# Adafruit_BQ24074.net
KiCad netlist of a schematic drawn in EAGLE
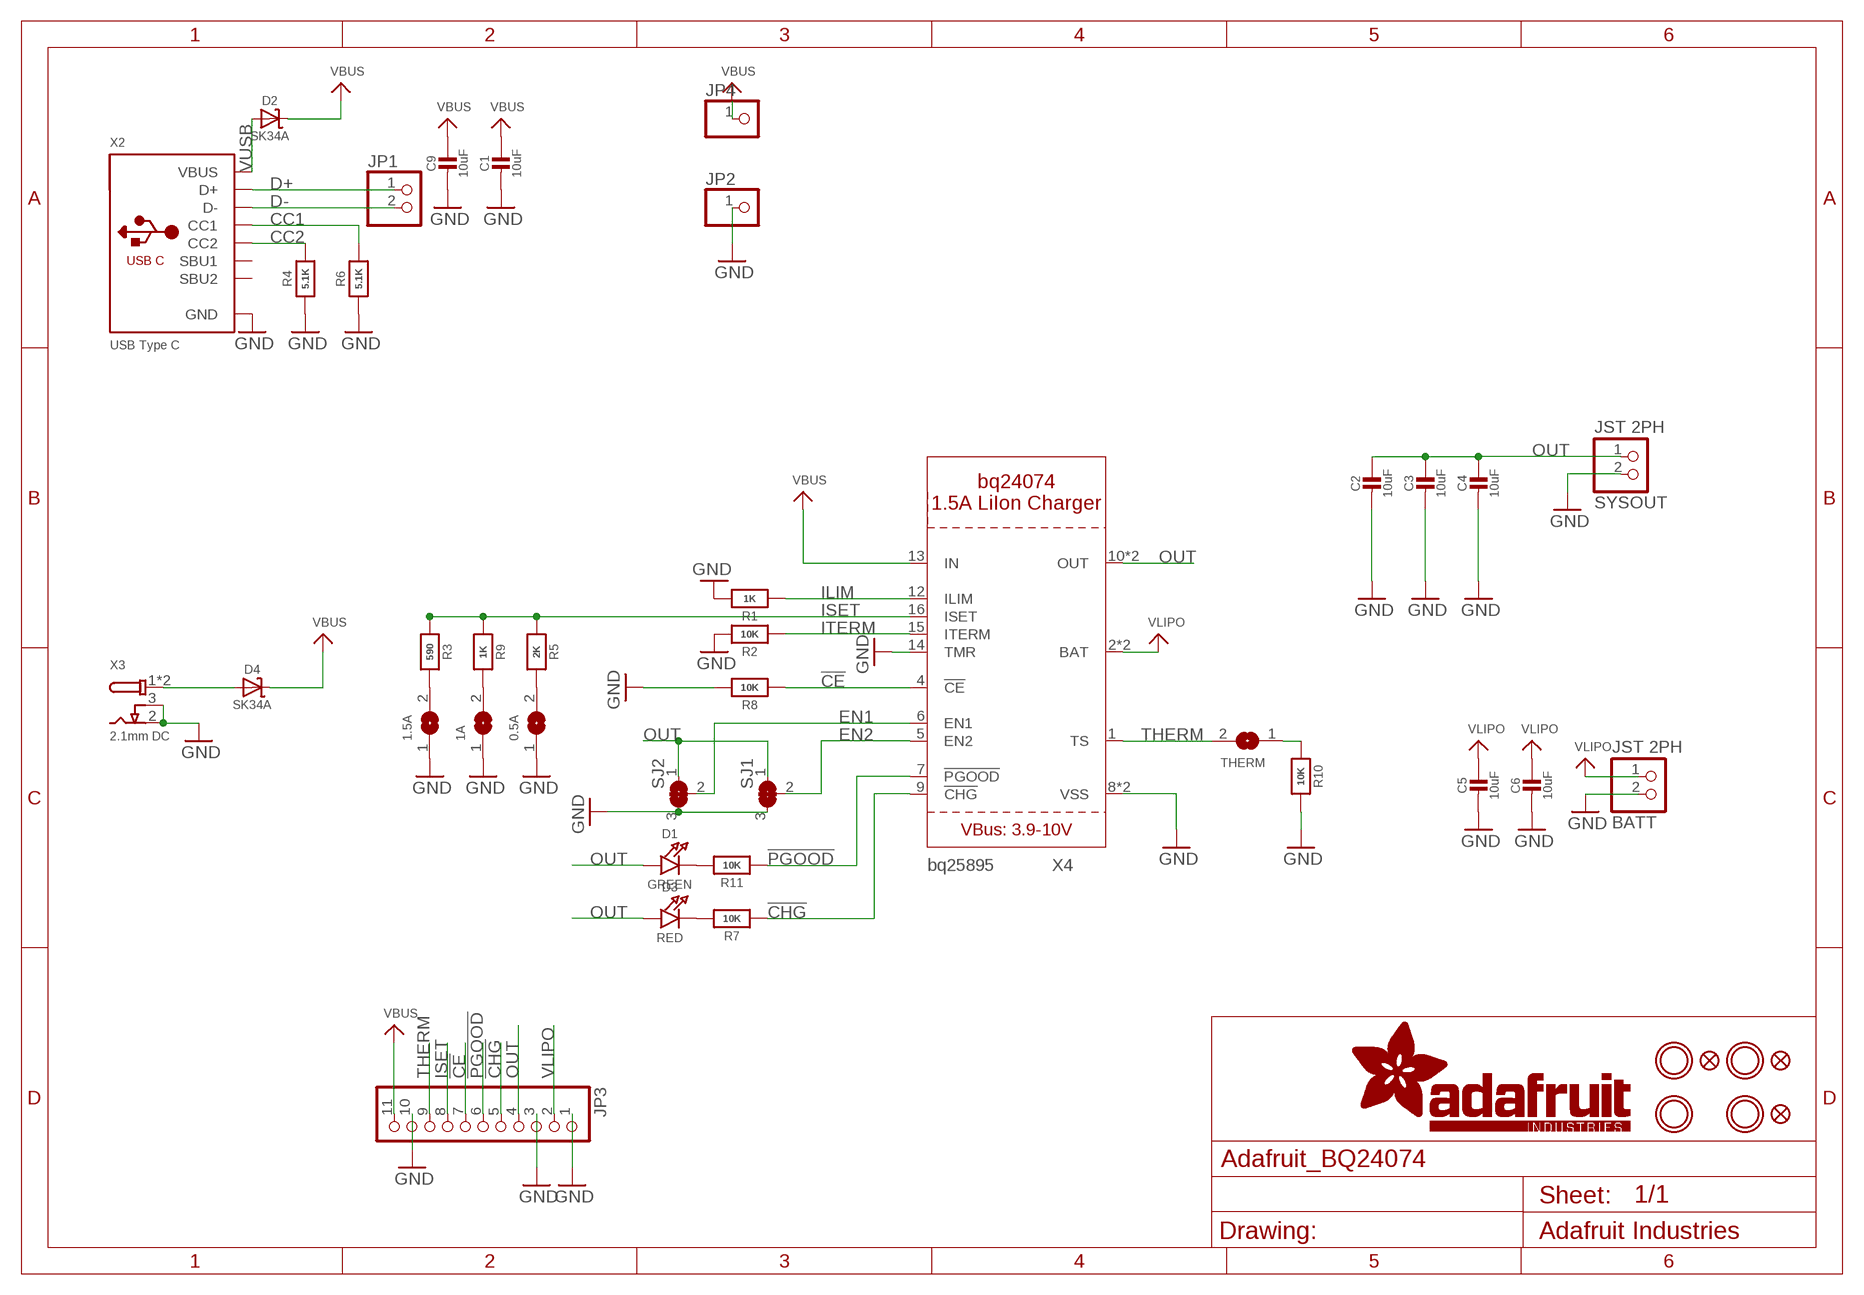
[diagram p0: schematic, sheet 1]

(export (version "E")
  (design (tool "Eeschema 10.0.6"))
  (components
    (comp (ref "0.5A")
      (value "SOLDERJUMPER")
      (footprint "eagle-import:SOLDERJUMPER_ARROW_NOPASTE")
      (libsource (lib "eagle-import") (part "SOLDERJUMPER"))
    )
    (comp (ref "1.5A")
      (value "SOLDERJUMPER")
      (footprint "eagle-import:SOLDERJUMPER_ARROW_NOPASTE")
      (libsource (lib "eagle-import") (part "SOLDERJUMPER"))
    )
    (comp (ref "1A")
      (value "SOLDERJUMPERCLOSED")
      (footprint "eagle-import:SOLDERJUMPER_CLOSEDWIRE")
      (libsource (lib "eagle-import") (part "SOLDERJUMPERCLOSED"))
    )
    (comp (ref "BATT")
      (value "JST 2PH")
      (footprint "eagle-import:JST-PH-2-SMT-RA")
      (libsource (lib "eagle-import") (part "JST_2PIN-SMT-RA"))
    )
    (comp (ref "C1")
      (value "10uF")
      (footprint "eagle-import:0805-NO")
      (libsource (lib "eagle-import") (part "CAP_CERAMIC0805-NOOUTLINE"))
    )
    (comp (ref "C2")
      (value "10uF")
      (footprint "eagle-import:0805-NO")
      (libsource (lib "eagle-import") (part "CAP_CERAMIC0805-NOOUTLINE"))
    )
    (comp (ref "C3")
      (value "10uF")
      (footprint "eagle-import:0805-NO")
      (libsource (lib "eagle-import") (part "CAP_CERAMIC0805-NOOUTLINE"))
    )
    (comp (ref "C4")
      (value "10uF")
      (footprint "eagle-import:0805-NO")
      (libsource (lib "eagle-import") (part "CAP_CERAMIC0805-NOOUTLINE"))
    )
    (comp (ref "C5")
      (value "10uF")
      (footprint "eagle-import:0805-NO")
      (libsource (lib "eagle-import") (part "CAP_CERAMIC0805-NOOUTLINE"))
    )
    (comp (ref "C6")
      (value "10uF")
      (footprint "eagle-import:0805-NO")
      (libsource (lib "eagle-import") (part "CAP_CERAMIC0805-NOOUTLINE"))
    )
    (comp (ref "C9")
      (value "10uF")
      (footprint "eagle-import:0805-NO")
      (libsource (lib "eagle-import") (part "CAP_CERAMIC0805-NOOUTLINE"))
    )
    (comp (ref "D1")
      (value "GREEN")
      (footprint "eagle-import:CHIPLED_0603")
      (libsource (lib "eagle-import") (part "LED0603"))
    )
    (comp (ref "D2")
      (value "SK34A")
      (footprint "eagle-import:SMADIODE")
      (libsource (lib "eagle-import") (part "DIODE-SCHOTTKYSMA"))
    )
    (comp (ref "D3")
      (value "RED")
      (footprint "eagle-import:CHIPLED_0603")
      (libsource (lib "eagle-import") (part "LED0603"))
    )
    (comp (ref "D4")
      (value "SK34A")
      (footprint "eagle-import:SMADIODE")
      (libsource (lib "eagle-import") (part "DIODE-SCHOTTKYSMA"))
    )
    (comp (ref "FID1")
      (value "FIDUCIAL_1MM")
      (footprint "eagle-import:FIDUCIAL_1MM")
      (libsource (lib "eagle-import") (part "FIDUCIAL_1MM"))
    )
    (comp (ref "FID2")
      (value "FIDUCIAL_1MM")
      (footprint "eagle-import:FIDUCIAL_1MM")
      (libsource (lib "eagle-import") (part "FIDUCIAL_1MM"))
    )
    (comp (ref "FID3")
      (value "FIDUCIAL_1MM")
      (footprint "eagle-import:FIDUCIAL_1MM")
      (libsource (lib "eagle-import") (part "FIDUCIAL_1MM"))
    )
    (comp (ref "JP1")
      (value "HEADER-1X2ROUND")
      (footprint "eagle-import:1X02_ROUND")
      (libsource (lib "eagle-import") (part "HEADER-1X2ROUND"))
    )
    (comp (ref "JP2")
      (value "HEADER-1X1")
      (footprint "eagle-import:1X01_OVAL")
      (libsource (lib "eagle-import") (part "HEADER-1X1"))
    )
    (comp (ref "JP3")
      (value "HEADER-1X1176MIL")
      (footprint "eagle-import:1X11_ROUND_76")
      (libsource (lib "eagle-import") (part "HEADER-1X1176MIL"))
    )
    (comp (ref "JP4")
      (value "HEADER-1X1")
      (footprint "eagle-import:1X01_OVAL")
      (libsource (lib "eagle-import") (part "HEADER-1X1"))
    )
    (comp (ref "R1")
      (value "1K")
      (footprint "eagle-import:0603-NO")
      (libsource (lib "eagle-import") (part "RESISTOR_0603_NOOUT"))
    )
    (comp (ref "R2")
      (value "10K")
      (footprint "eagle-import:0603-NO")
      (libsource (lib "eagle-import") (part "RESISTOR_0603_NOOUT"))
    )
    (comp (ref "R3")
      (value "590")
      (footprint "eagle-import:0603-NO")
      (libsource (lib "eagle-import") (part "RESISTOR_0603_NOOUT"))
    )
    (comp (ref "R4")
      (value "5.1K")
      (footprint "eagle-import:0603-NO")
      (libsource (lib "eagle-import") (part "RESISTOR_0603_NOOUT"))
    )
    (comp (ref "R5")
      (value "2K")
      (footprint "eagle-import:0603-NO")
      (libsource (lib "eagle-import") (part "RESISTOR_0603_NOOUT"))
    )
    (comp (ref "R6")
      (value "5.1K")
      (footprint "eagle-import:0603-NO")
      (libsource (lib "eagle-import") (part "RESISTOR_0603_NOOUT"))
    )
    (comp (ref "R7")
      (value "10K")
      (footprint "eagle-import:0603-NO")
      (libsource (lib "eagle-import") (part "RESISTOR_0603_NOOUT"))
    )
    (comp (ref "R8")
      (value "10K")
      (footprint "eagle-import:0603-NO")
      (libsource (lib "eagle-import") (part "RESISTOR_0603_NOOUT"))
    )
    (comp (ref "R9")
      (value "1K")
      (footprint "eagle-import:0603-NO")
      (libsource (lib "eagle-import") (part "RESISTOR_0603_NOOUT"))
    )
    (comp (ref "R10")
      (value "10K")
      (footprint "eagle-import:0603-NO")
      (libsource (lib "eagle-import") (part "RESISTOR_0603_NOOUT"))
    )
    (comp (ref "R11")
      (value "10K")
      (footprint "eagle-import:0603-NO")
      (libsource (lib "eagle-import") (part "RESISTOR_0603_NOOUT"))
    )
    (comp (ref "SJ1")
      (value "SOLDERJUMPER_2WAY")
      (footprint "eagle-import:SOLDERJUMPER_2WAY_OPEN_NOPASTE")
      (libsource (lib "eagle-import") (part "SOLDERJUMPER_2WAY"))
    )
    (comp (ref "SJ2")
      (value "SOLDERJUMPER_2WAY")
      (footprint "eagle-import:SOLDERJUMPER_2WAY_OPEN_NOPASTE")
      (libsource (lib "eagle-import") (part "SOLDERJUMPER_2WAY"))
    )
    (comp (ref "SYSOUT")
      (value "JST 2PH")
      (footprint "eagle-import:JST-PH-2-SMT-RA")
      (libsource (lib "eagle-import") (part "JST_2PIN-SMT-RA"))
    )
    (comp (ref "THERM")
      (value "SOLDERJUMPERCLOSED")
      (footprint "eagle-import:SOLDERJUMPER_CLOSEDWIRE")
      (libsource (lib "eagle-import") (part "SOLDERJUMPERCLOSED"))
    )
    (comp (ref "U$3")
      (value "MOUNTINGHOLE2.5")
      (footprint "eagle-import:MOUNTINGHOLE_2.5_PLATED")
      (libsource (lib "eagle-import") (part "MOUNTINGHOLE2.5"))
    )
    (comp (ref "U$4")
      (value "MOUNTINGHOLE2.5")
      (footprint "eagle-import:MOUNTINGHOLE_2.5_PLATED")
      (libsource (lib "eagle-import") (part "MOUNTINGHOLE2.5"))
    )
    (comp (ref "U$11")
      (value "MOUNTINGHOLE2.5")
      (footprint "eagle-import:MOUNTINGHOLE_2.5_PLATED")
      (libsource (lib "eagle-import") (part "MOUNTINGHOLE2.5"))
    )
    (comp (ref "U$12")
      (value "MOUNTINGHOLE2.5")
      (footprint "eagle-import:MOUNTINGHOLE_2.5_PLATED")
      (libsource (lib "eagle-import") (part "MOUNTINGHOLE2.5"))
    )
    (comp (ref "X2")
      (value "USB Type C")
      (footprint "eagle-import:USB_C_CUSB31-CFM2AX-01-X")
      (libsource (lib "eagle-import") (part "USB_C"))
    )
    (comp (ref "X3")
      (value "2.1mm DC")
      (footprint "eagle-import:DCJACK_2MM_SMT")
      (libsource (lib "eagle-import") (part "DCBARRELSMT"))
    )
    (comp (ref "X4")
      (value "BQ24074")
      (footprint "eagle-import:QFN16_3MM")
      (libsource (lib "eagle-import") (part "BQ24074"))
    )
  )
  (nets
    (net (code "1") (name "/CC1") (class "Default")
      (node (ref "R6") (pin "2") (pinfunction "2_2") (pintype "passive"))
      (node (ref "X2") (pin "A5") (pinfunction "CC1_A5") (pintype "bidirectional"))
    )
    (net (code "2") (name "/CC2") (class "Default")
      (node (ref "R4") (pin "2") (pinfunction "2_2") (pintype "passive"))
      (node (ref "X2") (pin "B5") (pinfunction "CC2_B5") (pintype "bidirectional"))
    )
    (net (code "3") (name "/D+") (class "Default")
      (node (ref "JP1") (pin "1") (pinfunction "1_1") (pintype "passive"))
      (node (ref "X2") (pin "A6") (pinfunction "D+_A6") (pintype "bidirectional"))
      (node (ref "X2") (pin "B6") (pinfunction "D+_B6") (pintype "bidirectional"))
    )
    (net (code "4") (name "/D-") (class "Default")
      (node (ref "JP1") (pin "2") (pinfunction "2_2") (pintype "passive"))
      (node (ref "X2") (pin "A7") (pinfunction "D-_A7") (pintype "bidirectional"))
      (node (ref "X2") (pin "B7") (pinfunction "D-_B7") (pintype "bidirectional"))
    )
    (net (code "5") (name "/EN1") (class "Default")
      (node (ref "SJ2") (pin "2") (pinfunction "2_2") (pintype "passive"))
      (node (ref "X4") (pin "6") (pinfunction "EN1_6") (pintype "input"))
    )
    (net (code "6") (name "/EN2") (class "Default")
      (node (ref "SJ1") (pin "2") (pinfunction "2_2") (pintype "passive"))
      (node (ref "X4") (pin "5") (pinfunction "EN2_5") (pintype "input"))
    )
    (net (code "7") (name "/ILIM") (class "Default")
      (node (ref "R1") (pin "1") (pinfunction "1_1") (pintype "passive"))
      (node (ref "X4") (pin "12") (pinfunction "ILIM_12") (pintype "input"))
    )
    (net (code "8") (name "/ISET") (class "Default")
      (node (ref "JP3") (pin "8") (pinfunction "8_8") (pintype "passive"))
      (node (ref "R3") (pin "1") (pinfunction "1_1") (pintype "passive"))
      (node (ref "R5") (pin "1") (pinfunction "1_1") (pintype "passive"))
      (node (ref "R9") (pin "1") (pinfunction "1_1") (pintype "passive"))
      (node (ref "X4") (pin "16") (pinfunction "ISET_16") (pintype "input"))
    )
    (net (code "9") (name "/ITERM") (class "Default")
      (node (ref "R2") (pin "1") (pinfunction "1_1") (pintype "passive"))
      (node (ref "X4") (pin "15") (pinfunction "ITERM_15") (pintype "input"))
    )
    (net (code "10") (name "/OUT") (class "Default")
      (node (ref "C2") (pin "1") (pinfunction "1_1") (pintype "passive"))
      (node (ref "C3") (pin "1") (pinfunction "1_1") (pintype "passive"))
      (node (ref "C4") (pin "1") (pinfunction "1_1") (pintype "passive"))
      (node (ref "D1") (pin "A") (pinfunction "A_A") (pintype "passive"))
      (node (ref "D3") (pin "A") (pinfunction "A_A") (pintype "passive"))
      (node (ref "JP3") (pin "4") (pinfunction "4_4") (pintype "passive"))
      (node (ref "SJ1") (pin "1") (pinfunction "1_1") (pintype "passive"))
      (node (ref "SJ2") (pin "1") (pinfunction "1_1") (pintype "passive"))
      (node (ref "SYSOUT") (pin "1") (pinfunction "2_1") (pintype "passive"))
      (node (ref "X4") (pin "10") (pinfunction "OUT_10") (pintype "output"))
      (node (ref "X4") (pin "11") (pinfunction "OUT_11") (pintype "output"))
    )
    (net (code "11") (name "/THERM") (class "Default")
      (node (ref "JP3") (pin "9") (pinfunction "9_9") (pintype "passive"))
      (node (ref "THERM") (pin "2") (pinfunction "2_2") (pintype "passive"))
      (node (ref "X4") (pin "1") (pinfunction "TS_1") (pintype "input"))
    )
    (net (code "12") (name "/VUSB") (class "Default")
      (node (ref "D2") (pin "A") (pinfunction "A_A") (pintype "passive"))
      (node (ref "X2") (pin "A4B9") (pinfunction "VBUS_A4B9") (pintype "power_in"))
      (node (ref "X2") (pin "B4A9") (pinfunction "VBUS_B4A9") (pintype "power_in"))
    )
    (net (code "13") (name "/~{CE}") (class "Default")
      (node (ref "JP3") (pin "7") (pinfunction "7_7") (pintype "passive"))
      (node (ref "R8") (pin "1") (pinfunction "1_1") (pintype "passive"))
      (node (ref "X4") (pin "4") (pinfunction "~{CE}_4") (pintype "input"))
    )
    (net (code "14") (name "/~{CHG}") (class "Default")
      (node (ref "JP3") (pin "5") (pinfunction "5_5") (pintype "passive"))
      (node (ref "R7") (pin "1") (pinfunction "1_1") (pintype "passive"))
      (node (ref "X4") (pin "9") (pinfunction "~{CHG}_9") (pintype "output"))
    )
    (net (code "15") (name "/~{PGOOD}") (class "Default")
      (node (ref "JP3") (pin "6") (pinfunction "6_6") (pintype "passive"))
      (node (ref "R11") (pin "1") (pinfunction "1_1") (pintype "passive"))
      (node (ref "X4") (pin "7") (pinfunction "~{PGOOD}_7") (pintype "output"))
    )
    (net (code "16") (name "GND") (class "Default")
      (node (ref "0.5A") (pin "1") (pinfunction "1_1") (pintype "passive"))
      (node (ref "1.5A") (pin "1") (pinfunction "1_1") (pintype "passive"))
      (node (ref "1A") (pin "1") (pinfunction "1_1") (pintype "passive"))
      (node (ref "BATT") (pin "2") (pinfunction "1_2") (pintype "passive"))
      (node (ref "C1") (pin "2") (pinfunction "2_2") (pintype "passive"))
      (node (ref "C2") (pin "2") (pinfunction "2_2") (pintype "passive"))
      (node (ref "C3") (pin "2") (pinfunction "2_2") (pintype "passive"))
      (node (ref "C4") (pin "2") (pinfunction "2_2") (pintype "passive"))
      (node (ref "C5") (pin "2") (pinfunction "2_2") (pintype "passive"))
      (node (ref "C6") (pin "2") (pinfunction "2_2") (pintype "passive"))
      (node (ref "C9") (pin "2") (pinfunction "2_2") (pintype "passive"))
      (node (ref "JP2") (pin "1") (pinfunction "1_1") (pintype "passive"))
      (node (ref "JP3") (pin "1") (pinfunction "1_1") (pintype "passive"))
      (node (ref "JP3") (pin "10") (pinfunction "10_10") (pintype "passive"))
      (node (ref "JP3") (pin "3") (pinfunction "3_3") (pintype "passive"))
      (node (ref "R1") (pin "2") (pinfunction "2_2") (pintype "passive"))
      (node (ref "R10") (pin "2") (pinfunction "2_2") (pintype "passive"))
      (node (ref "R2") (pin "2") (pinfunction "2_2") (pintype "passive"))
      (node (ref "R4") (pin "1") (pinfunction "1_1") (pintype "passive"))
      (node (ref "R6") (pin "1") (pinfunction "1_1") (pintype "passive"))
      (node (ref "R8") (pin "2") (pinfunction "2_2") (pintype "passive"))
      (node (ref "SJ1") (pin "3") (pinfunction "3_3") (pintype "passive"))
      (node (ref "SJ2") (pin "3") (pinfunction "3_3") (pintype "passive"))
      (node (ref "SYSOUT") (pin "2") (pinfunction "1_2") (pintype "passive"))
      (node (ref "X2") (pin "A1B12") (pinfunction "GND_A1B12") (pintype "power_in"))
      (node (ref "X2") (pin "B1A12") (pinfunction "GND_B1A12") (pintype "power_in"))
      (node (ref "X3") (pin "2") (pinfunction "GND_2") (pintype "power_in"))
      (node (ref "X3") (pin "3") (pinfunction "GNDBREAK_3") (pintype "power_in"))
      (node (ref "X4") (pin "14") (pinfunction "TMR_14") (pintype "input"))
      (node (ref "X4") (pin "8") (pinfunction "VSS_8") (pintype "power_in"))
      (node (ref "X4") (pin "THERMAL") (pinfunction "VSS_THERMAL") (pintype "power_in"))
    )
    (net (code "17") (name "Net-(0.5A-Pad2)") (class "Default")
      (node (ref "0.5A") (pin "2") (pinfunction "2_2") (pintype "passive"))
      (node (ref "R5") (pin "2") (pinfunction "2_2") (pintype "passive"))
    )
    (net (code "18") (name "Net-(1.5A-Pad2)") (class "Default")
      (node (ref "1.5A") (pin "2") (pinfunction "2_2") (pintype "passive"))
      (node (ref "R3") (pin "2") (pinfunction "2_2") (pintype "passive"))
    )
    (net (code "19") (name "Net-(1A-Pad2)") (class "Default")
      (node (ref "1A") (pin "2") (pinfunction "2_2") (pintype "passive"))
      (node (ref "R9") (pin "2") (pinfunction "2_2") (pintype "passive"))
    )
    (net (code "20") (name "Net-(D1-PadC)") (class "Default")
      (node (ref "D1") (pin "C") (pinfunction "C_C") (pintype "passive"))
      (node (ref "R11") (pin "2") (pinfunction "2_2") (pintype "passive"))
    )
    (net (code "21") (name "Net-(D3-PadC)") (class "Default")
      (node (ref "D3") (pin "C") (pinfunction "C_C") (pintype "passive"))
      (node (ref "R7") (pin "2") (pinfunction "2_2") (pintype "passive"))
    )
    (net (code "22") (name "Net-(D4-PadA)") (class "Default")
      (node (ref "D4") (pin "A") (pinfunction "A_A") (pintype "passive"))
      (node (ref "X3") (pin "1") (pinfunction "PWR_1") (pintype "power_in"))
      (node (ref "X3") (pin "1'") (pinfunction "PWR_1'") (pintype "power_in"))
    )
    (net (code "23") (name "Net-(R10-Pad1)") (class "Default")
      (node (ref "R10") (pin "1") (pinfunction "1_1") (pintype "passive"))
      (node (ref "THERM") (pin "1") (pinfunction "1_1") (pintype "passive"))
    )
    (net (code "24") (name "VBUS") (class "Default")
      (node (ref "C1") (pin "1") (pinfunction "1_1") (pintype "passive"))
      (node (ref "C9") (pin "1") (pinfunction "1_1") (pintype "passive"))
      (node (ref "D2") (pin "C") (pinfunction "C_C") (pintype "passive"))
      (node (ref "D4") (pin "C") (pinfunction "C_C") (pintype "passive"))
      (node (ref "JP3") (pin "11") (pinfunction "11_11") (pintype "passive"))
      (node (ref "JP4") (pin "1") (pinfunction "1_1") (pintype "passive"))
      (node (ref "X4") (pin "13") (pinfunction "IN_13") (pintype "power_in"))
    )
    (net (code "25") (name "VLIPO") (class "Default")
      (node (ref "BATT") (pin "1") (pinfunction "2_1") (pintype "passive"))
      (node (ref "C5") (pin "1") (pinfunction "1_1") (pintype "passive"))
      (node (ref "C6") (pin "1") (pinfunction "1_1") (pintype "passive"))
      (node (ref "JP3") (pin "2") (pinfunction "2_2") (pintype "passive"))
      (node (ref "X4") (pin "2") (pinfunction "BAT_2") (pintype "input"))
      (node (ref "X4") (pin "3") (pinfunction "BAT_3") (pintype "input"))
    )
    (net (code "26") (name "unconnected-(X2-SBU1-PadA8)") (class "Default")
      (node (ref "X2") (pin "A8") (pinfunction "SBU1_A8") (pintype "bidirectional"))
    )
    (net (code "27") (name "unconnected-(X2-SBU2-PadB8)") (class "Default")
      (node (ref "X2") (pin "B8") (pinfunction "SBU2_B8") (pintype "bidirectional"))
    )
  )
)
